# USBInterface.net
KiCad netlist of a schematic drawn in Altium Designer
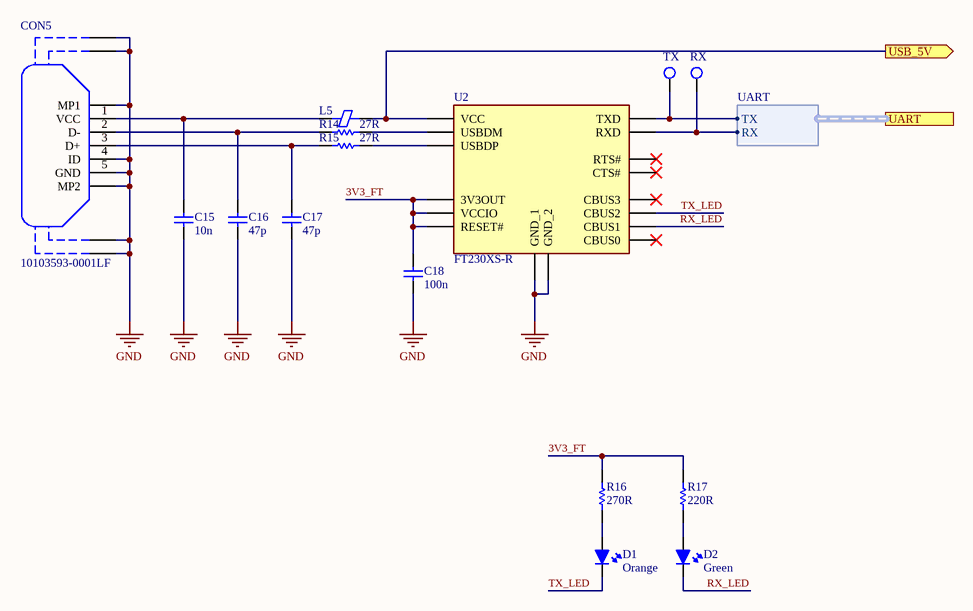
[diagram p0: USBInterface.SchDoc]

(export (version "E")
  (design (tool "Eeschema 10.0.6"))
  (components
    (comp (ref "C15")
      (value "10n")
      (footprint "Cap_0603_MD_outline")
      (description "Capacitor")
      (fields (field (name "MPN") "GRM188R72A103KA01"))
      (libsource (lib "LibPassive") (part "Capacitor"))
    )
    (comp (ref "C16")
      (value "47p")
      (footprint "Cap_0402_MD_outline")
      (description "Capacitor")
      (fields (field (name "MPN") "VJ0402A470JXXCW1BC"))
      (libsource (lib "LibPassive") (part "Capacitor"))
    )
    (comp (ref "C17")
      (value "47p")
      (footprint "Cap_0402_MD_outline")
      (description "Capacitor")
      (fields (field (name "MPN") "VJ0402A470JXXCW1BC"))
      (libsource (lib "LibPassive") (part "Capacitor"))
    )
    (comp (ref "C18")
      (value "100n")
      (footprint "Cap_0603_MD_outline")
      (description "Capacitor")
      (fields (field (name "MPN") "GRM188R72A104KA35"))
      (libsource (lib "LibPassive") (part "Capacitor"))
    )
    (comp (ref "CON5")
      (value "10103593-0001LF")
      (footprint "101035930001LF")
      (description "USB Connector")
      (fields (field (name "MOUSER PART NUMBER") "649-10103593-0001LF"))
      (libsource (lib "Library") (part "10103593-0001LF"))
    )
    (comp (ref "D1")
      (value "Orange")
      (footprint "LED_0805_OUTLINE")
      (description "LED")
      (fields (field (name "MPN") "599-0130-007F"))
      (libsource (lib "Library") (part "LED"))
    )
    (comp (ref "D2")
      (value "Green")
      (footprint "LED_0805_OUTLINE")
      (description "LED")
      (fields (field (name "MPN") "599-0181-007F"))
      (libsource (lib "Library") (part "LED"))
    )
    (comp (ref "L5")
      (value "~")
      (footprint "Bead_0805_MD_outline")
      (description "Ferrite bead")
      (fields (field (name "MPN") "MPZ2012S601AT000"))
      (libsource (lib "LibPassive") (part "Bead"))
    )
    (comp (ref "R14")
      (value "27R")
      (footprint "Res_0603_MD_outline")
      (description "Resistor")
      (fields (field (name "MPN") "MCT06030C2709FP500"))
      (libsource (lib "LibPassive") (part "Resistor"))
    )
    (comp (ref "R15")
      (value "27R")
      (footprint "Res_0603_MD_outline")
      (description "Resistor")
      (fields (field (name "MPN") "MCT06030C2709FP500"))
      (libsource (lib "LibPassive") (part "Resistor"))
    )
    (comp (ref "R16")
      (value "270R")
      (footprint "Res_0805_MD_outline")
      (description "Resistor")
      (fields (field (name "MPN") "RCS0805270RFKEA"))
      (libsource (lib "LibPassive") (part "Resistor"))
    )
    (comp (ref "R17")
      (value "220R")
      (footprint "Res_0805_MD_outline")
      (description "Resistor")
      (fields (field (name "MPN") "RCS0805220RFKEA"))
      (libsource (lib "LibPassive") (part "Resistor"))
    )
    (comp (ref "TP8")
      (value "TX")
      (footprint "TP_SQ25x40")
      (description "Test point")
      (libsource (lib "Library") (part "TestPoint"))
    )
    (comp (ref "TP9")
      (value "RX")
      (footprint "TP_SQ25x40")
      (description "Test point")
      (libsource (lib "Library") (part "TestPoint"))
    )
    (comp (ref "U2")
      (value "FT230XS-R")
      (footprint "SOP64P599X175-16N")
      (description "USB converter")
      (fields (field (name "MOUSER PART NUMBER") "895-FT230XS-R"))
      (libsource (lib "Library") (part "FT230XS-R"))
    )
  )
  (nets
    (net (code "2") (name "/3V3_FT") (class "Default")
      (node (ref "C18") (pin "2") (pinfunction "2_2") (pintype "passive"))
      (node (ref "R16") (pin "2") (pinfunction "2_2") (pintype "passive"))
      (node (ref "R17") (pin "2") (pinfunction "2_2") (pintype "passive"))
      (node (ref "U2") (pin "10") (pinfunction "3V3OUT_10") (pintype "passive"))
      (node (ref "U2") (pin "11") (pinfunction "RESET#_11") (pintype "passive"))
      (node (ref "U2") (pin "3") (pinfunction "VCCIO_3") (pintype "passive"))
    )
    (net (code "3") (name "/RX_LED") (class "Default")
      (node (ref "D2") (pin "K") (pinfunction "K_K") (pintype "passive"))
      (node (ref "U2") (pin "14") (pinfunction "CBUS1_14") (pintype "passive"))
    )
    (net (code "4") (name "/TX_LED") (class "Default")
      (node (ref "D1") (pin "K") (pinfunction "K_K") (pintype "passive"))
      (node (ref "U2") (pin "7") (pinfunction "CBUS2_7") (pintype "passive"))
    )
    (net (code "5") (name "/USB_5V") (class "Default")
      (node (ref "L5") (pin "2") (pintype "passive"))
      (node (ref "U2") (pin "12") (pinfunction "VCC_12") (pintype "passive"))
    )
    (net (code "7") (name "GND") (class "Default")
      (node (ref "C15") (pin "1") (pinfunction "1_1") (pintype "passive"))
      (node (ref "C16") (pin "1") (pinfunction "1_1") (pintype "passive"))
      (node (ref "C17") (pin "1") (pinfunction "1_1") (pintype "passive"))
      (node (ref "C18") (pin "1") (pinfunction "1_1") (pintype "passive"))
      (node (ref "CON5") (pin "4") (pinfunction "ID_4") (pintype "passive"))
      (node (ref "CON5") (pin "5") (pinfunction "GND_5") (pintype "passive"))
      (node (ref "CON5") (pin "MH1") (pinfunction "MH1_MH1") (pintype "passive"))
      (node (ref "CON5") (pin "MH2") (pinfunction "MH2_MH2") (pintype "passive"))
      (node (ref "CON5") (pin "MH3") (pinfunction "MH3_MH3") (pintype "passive"))
      (node (ref "CON5") (pin "MH4") (pinfunction "MH4_MH4") (pintype "passive"))
      (node (ref "CON5") (pin "MP1") (pinfunction "MP1_MP1") (pintype "passive"))
      (node (ref "CON5") (pin "MP2") (pinfunction "MP2_MP2") (pintype "passive"))
      (node (ref "U2") (pin "13") (pinfunction "GND_2_13") (pintype "passive"))
      (node (ref "U2") (pin "5") (pinfunction "GND_1_5") (pintype "passive"))
    )
    (net (code "8") (name "Net-(CON5-D+)") (class "Default")
      (node (ref "C17") (pin "2") (pinfunction "2_2") (pintype "passive"))
      (node (ref "CON5") (pin "3") (pinfunction "D+_3") (pintype "passive"))
      (node (ref "R15") (pin "1") (pinfunction "1_1") (pintype "passive"))
    )
    (net (code "9") (name "Net-(CON5-D-)") (class "Default")
      (node (ref "C16") (pin "2") (pinfunction "2_2") (pintype "passive"))
      (node (ref "CON5") (pin "2") (pinfunction "D-_2") (pintype "passive"))
      (node (ref "R14") (pin "1") (pinfunction "1_1") (pintype "passive"))
    )
    (net (code "10") (name "Net-(CON5-VCC)") (class "Default")
      (node (ref "C15") (pin "2") (pinfunction "2_2") (pintype "passive"))
      (node (ref "CON5") (pin "1") (pinfunction "VCC_1") (pintype "passive"))
      (node (ref "L5") (pin "1") (pintype "passive"))
    )
    (net (code "11") (name "Net-(D1-PadA)") (class "Default")
      (node (ref "D1") (pin "A") (pinfunction "A_A") (pintype "passive"))
      (node (ref "R16") (pin "1") (pinfunction "1_1") (pintype "passive"))
    )
    (net (code "12") (name "Net-(D2-PadA)") (class "Default")
      (node (ref "D2") (pin "A") (pinfunction "A_A") (pintype "passive"))
      (node (ref "R17") (pin "1") (pinfunction "1_1") (pintype "passive"))
    )
    (net (code "13") (name "Net-(U2-RXD)") (class "Default")
      (node (ref "TP9") (pin "1") (pintype "passive"))
      (node (ref "U2") (pin "4") (pinfunction "RXD_4") (pintype "passive"))
    )
    (net (code "14") (name "Net-(U2-TXD)") (class "Default")
      (node (ref "TP8") (pin "1") (pintype "passive"))
      (node (ref "U2") (pin "1") (pinfunction "TXD_1") (pintype "passive"))
    )
    (net (code "15") (name "Net-(U2-USBDM)") (class "Default")
      (node (ref "R14") (pin "2") (pinfunction "2_2") (pintype "passive"))
      (node (ref "U2") (pin "9") (pinfunction "USBDM_9") (pintype "passive"))
    )
    (net (code "16") (name "Net-(U2-USBDP)") (class "Default")
      (node (ref "R15") (pin "2") (pinfunction "2_2") (pintype "passive"))
      (node (ref "U2") (pin "8") (pinfunction "USBDP_8") (pintype "passive"))
    )
    (net (code "17") (name "unconnected-(U2-CBUS0-Pad15)") (class "Default")
      (node (ref "U2") (pin "15") (pinfunction "CBUS0_15") (pintype "passive+no_connect"))
    )
    (net (code "18") (name "unconnected-(U2-CBUS3-Pad16)") (class "Default")
      (node (ref "U2") (pin "16") (pinfunction "CBUS3_16") (pintype "passive+no_connect"))
    )
    (net (code "19") (name "unconnected-(U2-CTS#-Pad6)") (class "Default")
      (node (ref "U2") (pin "6") (pinfunction "CTS#_6") (pintype "passive+no_connect"))
    )
    (net (code "20") (name "unconnected-(U2-RTS#-Pad2)") (class "Default")
      (node (ref "U2") (pin "2") (pinfunction "RTS#_2") (pintype "passive+no_connect"))
    )
  )
)
